# analog_outputs_blk.net
KiCad netlist of a schematic drawn in Altium Designer
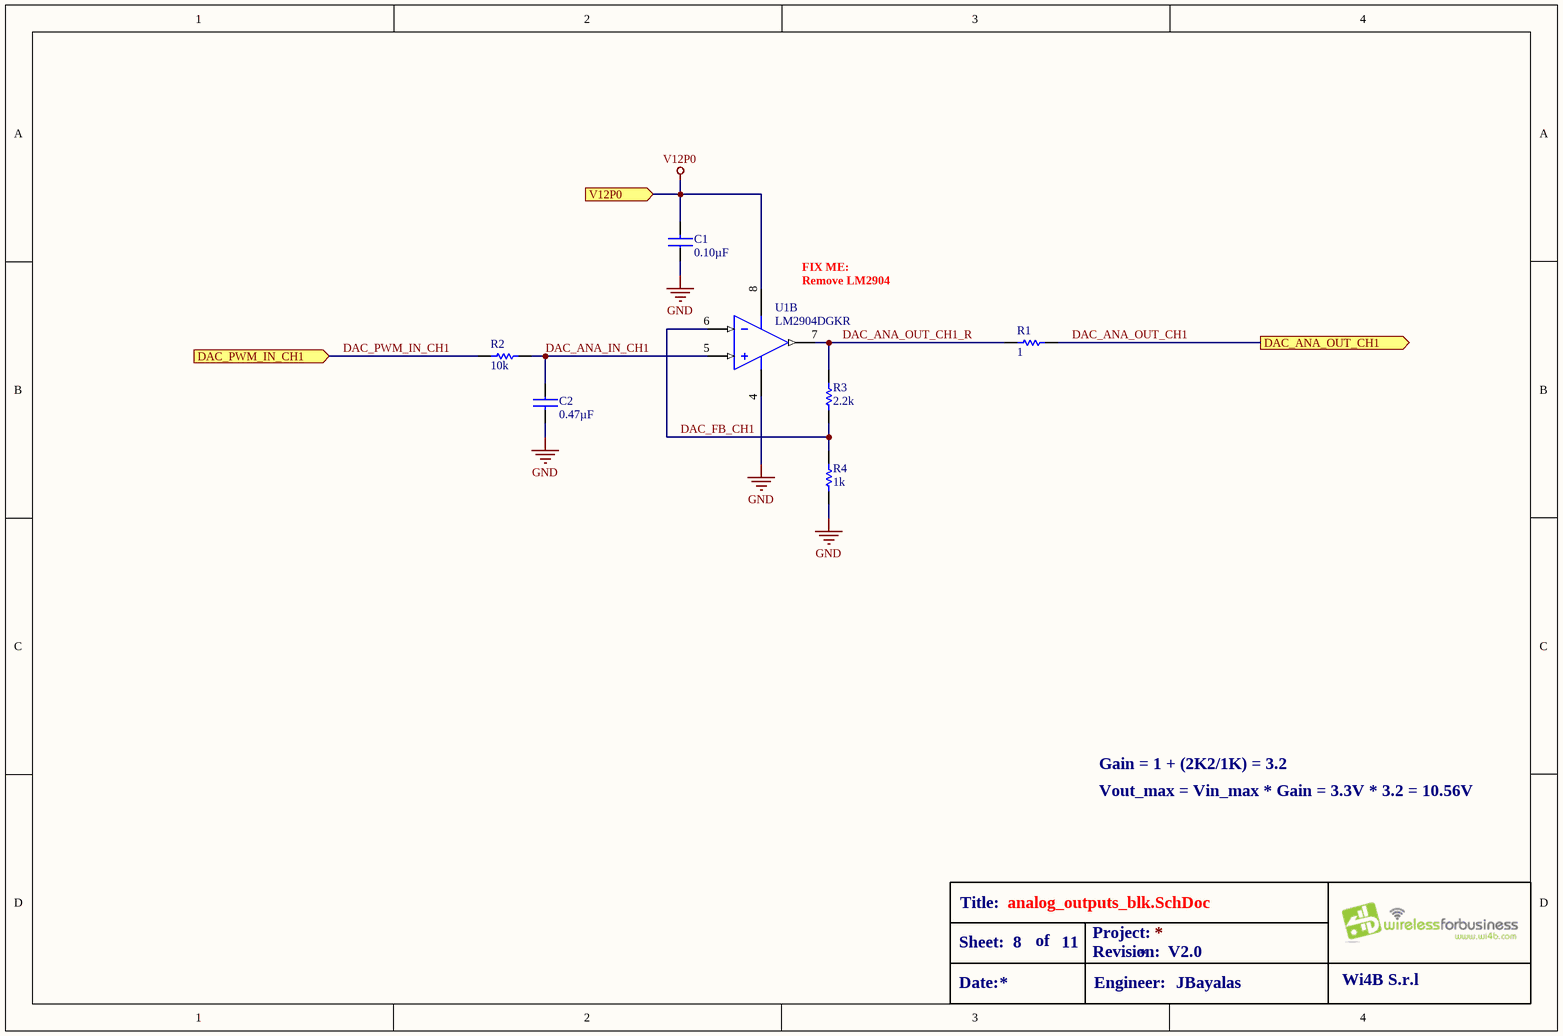
[diagram p0: analog_outputs_blk.SchDoc]

(export (version "E")
  (design (tool "Eeschema 10.0.6"))
  (components
    (comp (ref "C1")
      (value "0.10µF")
      (footprint "C0402")
      (description "CAP CER 0.1UF 50V X7R 0402")
      (fields (field (name "MPN") "GRM155R71H104ME14D"))
      (libsource (lib "Capacitor") (part "GRM155R71H104ME14D"))
    )
    (comp (ref "C2")
      (value "0.47µF")
      (footprint "C0603")
      (description "CAP CER 0.47UF 16V X7R 0603")
      (fields (field (name "MPN") "GRM188R71C474KA88D"))
      (libsource (lib "Capacitor") (part "GRM188R71C474KA88D"))
    )
    (comp (ref "R1")
      (value "1")
      (footprint "R0402")
      (description "RES SMD 1 OHM 1% 1/16W 0402")
      (fields (field (name "MPN") "CRCW04021R00FKED"))
      (libsource (lib "Res") (part "CRCW04021R00FKED"))
    )
    (comp (ref "R2")
      (value "10k")
      (footprint "R0402")
      (description "RES SMD 10K OHM 1% 1/10W 0402")
      (fields (field (name "MPN") "MCS04020C1002FE000"))
      (libsource (lib "Res") (part "MCS04020C1002FE000"))
    )
    (comp (ref "R3")
      (value "CRCW06032K20FKEA")
      (footprint "R0603")
      (description "RES SMD 2.2K OHM 1% 1/10W 0603")
      (fields
        (field (name "MANUFACTURER") "Vishay Dale")
        (field (name "TOLERANCE") "±1%")
        (field (name "RESISTANCE (OHMS)") "2.2k")
      )
      (libsource (lib "WiLamp") (part "CRCW06032K20FKEA"))
    )
    (comp (ref "R4")
      (value "1k")
      (footprint "R0402")
      (description "RES SMD 1K OHM 1% 1/10W 0402")
      (fields (field (name "MPN") "MCS04020C1001FE000"))
      (libsource (lib "Res") (part "MCS04020C1001FE000"))
    )
    (comp (ref "U1")
      (value "LM2904DGKR")
      (footprint "MSOP-8")
      (description "IC OPAMP GP 1.1MHZ 8SO")
      (fields (field (name "MPN") "LM2904DGKR"))
      (libsource (lib "IC") (part "LM2904DGKR"))
    )
  )
  (nets
    (net (code "1") (name "/DAC_ANA_IN_CH1") (class "Default")
      (node (ref "C2") (pin "1") (pinfunction "1_1") (pintype "passive"))
      (node (ref "R2") (pin "2") (pinfunction "2_2") (pintype "passive"))
      (node (ref "U1") (pin "5") (pinfunction "5_5") (pintype "input"))
    )
    (net (code "2") (name "/DAC_ANA_OUT_CH1") (class "Default")
      (node (ref "R1") (pin "2") (pinfunction "2_2") (pintype "passive"))
    )
    (net (code "3") (name "/DAC_ANA_OUT_CH1_R") (class "Default")
      (node (ref "R1") (pin "1") (pinfunction "1_1") (pintype "passive"))
      (node (ref "R3") (pin "2") (pinfunction "2_2") (pintype "passive"))
      (node (ref "U1") (pin "7") (pinfunction "7_7") (pintype "output"))
    )
    (net (code "4") (name "/DAC_FB_CH1") (class "Default")
      (node (ref "R3") (pin "1") (pinfunction "1_1") (pintype "passive"))
      (node (ref "R4") (pin "2") (pinfunction "2_2") (pintype "passive"))
      (node (ref "U1") (pin "6") (pinfunction "6_6") (pintype "input"))
    )
    (net (code "5") (name "/DAC_PWM_IN_CH1") (class "Default")
      (node (ref "R2") (pin "1") (pinfunction "1_1") (pintype "passive"))
    )
    (net (code "6") (name "GND") (class "Default")
      (node (ref "C1") (pin "1") (pinfunction "1_1") (pintype "passive"))
      (node (ref "C2") (pin "2") (pinfunction "2_2") (pintype "passive"))
      (node (ref "R4") (pin "1") (pinfunction "1_1") (pintype "passive"))
      (node (ref "U1") (pin "4") (pinfunction "4_4") (pintype "passive"))
    )
    (net (code "7") (name "V12P0") (class "Default")
      (node (ref "C1") (pin "2") (pinfunction "2_2") (pintype "passive"))
      (node (ref "U1") (pin "8") (pinfunction "8_8") (pintype "passive"))
    )
  )
)
